# Electronic_Theremin.net
KiCad netlist of a schematic drawn in Altium Designer
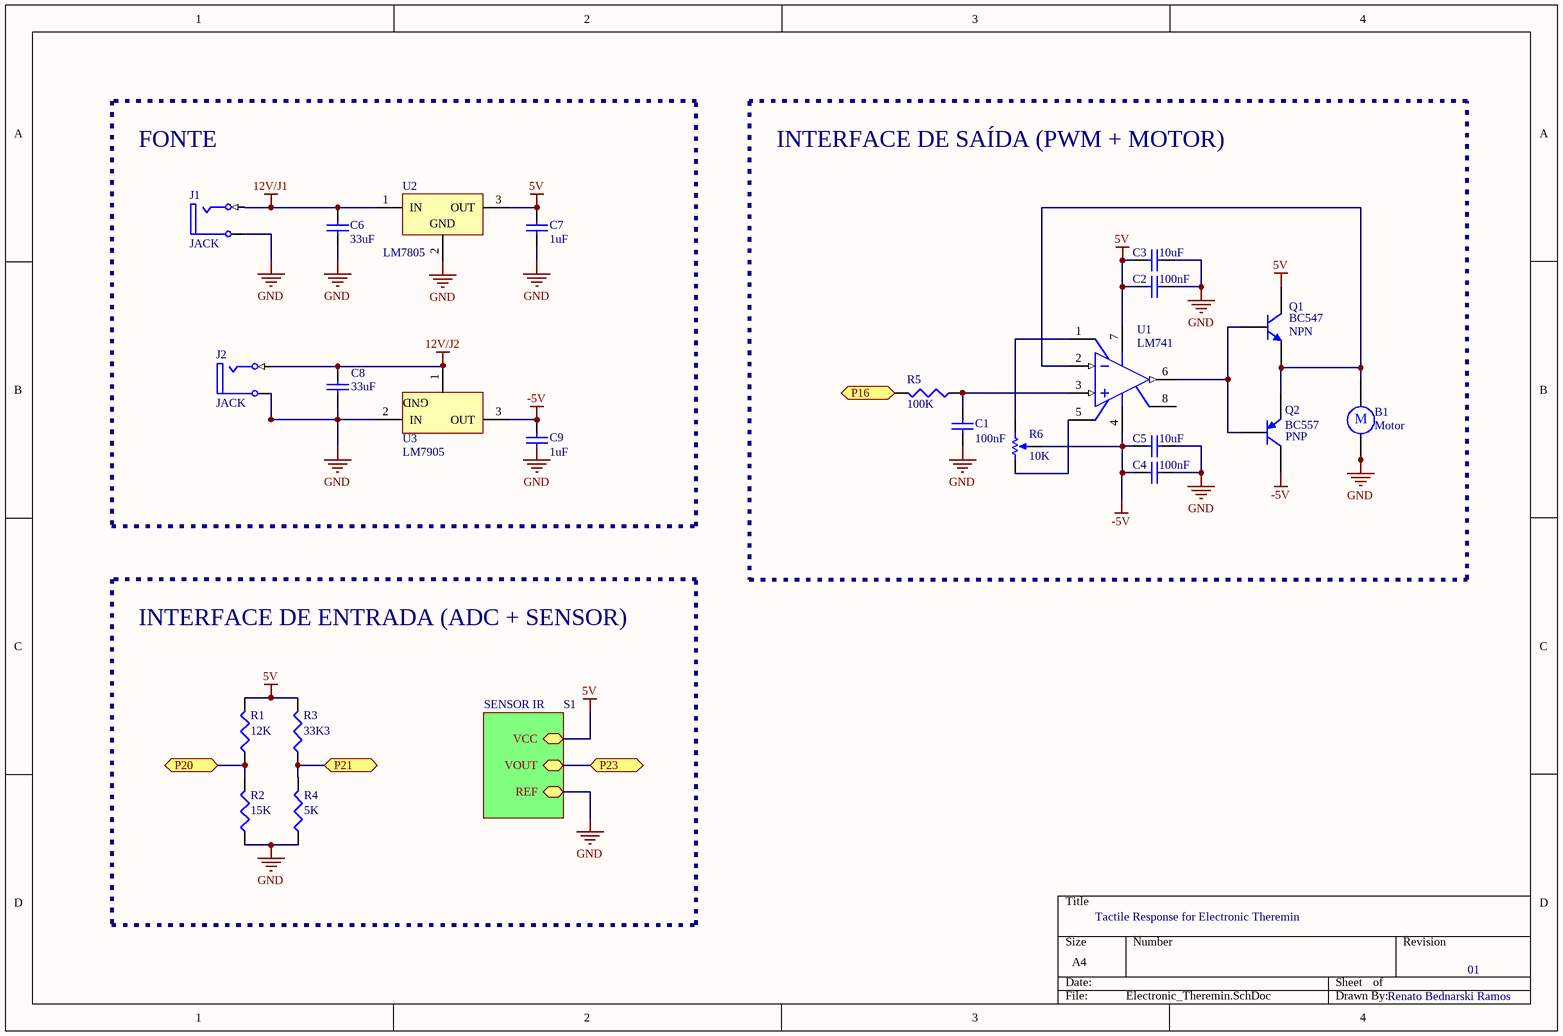
[diagram p0: Electronic_Theremin.SchDoc]

(export (version "E")
  (design (tool "Eeschema 10.0.6"))
  (components
    (comp (ref "B1")
      (value "Motor")
      (footprint "RB5-10.5")
      (description "Motor, General Kind")
      (fields (field (name "PUBLISHER") "Altium Limited"))
      (libsource (lib "Miscellaneous Devices") (part "Motor"))
    )
    (comp (ref "C1")
      (value "100nF")
      (footprint "RAD-0.3")
      (description "Capacitor")
      (fields (field (name "Comment") "Cap") (field (name "PUBLISHER") "Altium Limited"))
      (libsource (lib "Miscellaneous Devices") (part "Cap"))
    )
    (comp (ref "C2")
      (value "100nF")
      (footprint "RAD-0.3")
      (description "Capacitor")
      (fields (field (name "Comment") "Cap") (field (name "PUBLISHER") "Altium Limited"))
      (libsource (lib "Miscellaneous Devices") (part "Cap"))
    )
    (comp (ref "C3")
      (value "10uF")
      (footprint "RAD-0.3")
      (description "Capacitor")
      (fields (field (name "Comment") "Cap") (field (name "PUBLISHER") "Altium Limited"))
      (libsource (lib "Miscellaneous Devices") (part "Cap"))
    )
    (comp (ref "C4")
      (value "100nF")
      (footprint "RAD-0.3")
      (description "Capacitor")
      (fields (field (name "Comment") "Cap") (field (name "PUBLISHER") "Altium Limited"))
      (libsource (lib "Miscellaneous Devices") (part "Cap"))
    )
    (comp (ref "C5")
      (value "10uF")
      (footprint "RAD-0.3")
      (description "Capacitor")
      (fields (field (name "Comment") "Cap") (field (name "PUBLISHER") "Altium Limited"))
      (libsource (lib "Miscellaneous Devices") (part "Cap"))
    )
    (comp (ref "C6")
      (value "33uF")
      (footprint "RAD-0.3")
      (description "Capacitor")
      (fields (field (name "Comment") "Cap") (field (name "PUBLISHER") "Altium Limited"))
      (libsource (lib "Miscellaneous Devices") (part "Cap"))
    )
    (comp (ref "C7")
      (value "1uF")
      (footprint "RAD-0.3")
      (description "Capacitor")
      (fields (field (name "Comment") "Cap") (field (name "PUBLISHER") "Altium Limited"))
      (libsource (lib "Miscellaneous Devices") (part "Cap"))
    )
    (comp (ref "C8")
      (value "33uF")
      (footprint "RAD-0.3")
      (description "Capacitor")
      (fields (field (name "Comment") "Cap") (field (name "PUBLISHER") "Altium Limited"))
      (libsource (lib "Miscellaneous Devices") (part "Cap"))
    )
    (comp (ref "C9")
      (value "1uF")
      (footprint "RAD-0.3")
      (description "Capacitor")
      (fields (field (name "Comment") "Cap") (field (name "PUBLISHER") "Altium Limited"))
      (libsource (lib "Miscellaneous Devices") (part "Cap"))
    )
    (comp (ref "J1")
      (value "JACK")
      (footprint "JACK/6-V2")
      (description "Jack Socket, 1/4\" [6.5mm], Thru-Hole, Vertical, 2-Conductor Open Circuit")
      (fields (field (name "PUBLISHER") "Altium Limited"))
      (libsource (lib "Miscellaneous Connectors") (part "Phonejack2"))
    )
    (comp (ref "J2")
      (value "JACK")
      (footprint "JACK/6-V2")
      (description "Jack Socket, 1/4\" [6.5mm], Thru-Hole, Vertical, 2-Conductor Open Circuit")
      (fields (field (name "PUBLISHER") "Altium Limited"))
      (libsource (lib "Miscellaneous Connectors") (part "Phonejack2"))
    )
    (comp (ref "Q1")
      (value "NPN")
      (footprint "TO-226-AA")
      (description "NPN Bipolar Transistor")
      (fields (field (name "ALTIUM_VALUE") "BC547"))
      (libsource (lib "Miscellaneous Devices") (part "NPN"))
    )
    (comp (ref "Q2")
      (value "PNP")
      (footprint "SOT-23B_N")
      (description "PNP Bipolar Transistor")
      (fields (field (name "ALTIUM_VALUE") "BC557"))
      (libsource (lib "Miscellaneous Devices") (part "PNP"))
    )
    (comp (ref "R1")
      (value "12K")
      (footprint "J1-0603")
      (description "Resistor")
      (fields (field (name "Comment") "Res3") (field (name "PUBLISHER") "Altium Limited"))
      (libsource (lib "Miscellaneous Devices") (part "Res3"))
    )
    (comp (ref "R2")
      (value "15K")
      (footprint "J1-0603")
      (description "Resistor")
      (fields (field (name "Comment") "Res3") (field (name "PUBLISHER") "Altium Limited"))
      (libsource (lib "Miscellaneous Devices") (part "Res3"))
    )
    (comp (ref "R3")
      (value "33K3")
      (footprint "J1-0603")
      (description "Resistor")
      (fields (field (name "Comment") "Res3") (field (name "PUBLISHER") "Altium Limited"))
      (libsource (lib "Miscellaneous Devices") (part "Res3"))
    )
    (comp (ref "R4")
      (value "5K")
      (footprint "J1-0603")
      (description "Resistor")
      (fields (field (name "Comment") "Res3") (field (name "PUBLISHER") "Altium Limited"))
      (libsource (lib "Miscellaneous Devices") (part "Res3"))
    )
    (comp (ref "R5")
      (value "100K")
      (footprint "J1-0603")
      (description "Resistor")
      (fields (field (name "Comment") "Res3") (field (name "PUBLISHER") "Altium Limited"))
      (libsource (lib "Miscellaneous Devices") (part "Res3"))
    )
    (comp (ref "R6")
      (value "10K")
      (footprint "VR5")
      (description "Potentiometer")
      (fields (field (name "PUBLISHER") "Altium Limited"))
      (libsource (lib "Miscellaneous Devices") (part "RPot"))
    )
    (comp (ref "U1")
      (value "LM741")
      (footprint "N08E")
      (description "Operational Amplifier, 8-pin MDIP")
      (fields
        (field (name "PARTNUMBER") "LM741CN")
        (field (name "MANUFACTURER") "National Semiconductor")
        (field (name "PUBLISHER") "Altium Limited")
      )
      (libsource (lib "NSC Amplifier") (part "LM741CN"))
    )
    (comp (ref "U2")
      (value "LM7805")
      (footprint "KC03")
      (description "Positive-Voltage Regulator")
      (fields (field (name "PUBLISHER") "Altium Limited"))
      (libsource (lib "TI Power Mgt Voltage Regulator") (part "µA7805CKC"))
    )
    (comp (ref "U3")
      (value "LM7905")
      (footprint "T03B")
      (description "3-Terminal Negative Regulator, 3-pin TO-220")
      (fields
        (field (name "PARTNUMBER") "LM7905CT")
        (field (name "MANUFACTURER") "National Semiconductor")
        (field (name "PUBLISHER") "Altium Limited")
      )
      (libsource (lib "NSC LDO") (part "LM7905CT"))
    )
  )
  (nets
    (net (code "1") (name "-5V") (class "Default")
      (node (ref "C4") (pin "2") (pinfunction "2_2") (pintype "passive"))
      (node (ref "C5") (pin "2") (pinfunction "2_2") (pintype "passive"))
      (node (ref "C9") (pin "2") (pinfunction "2_2") (pintype "passive"))
      (node (ref "Q2") (pin "1") (pinfunction "C_1") (pintype "passive"))
      (node (ref "R6") (pin "3") (pinfunction "TAP_3") (pintype "passive"))
      (node (ref "U1") (pin "4") (pinfunction "V-_4") (pintype "power_in"))
      (node (ref "U3") (pin "3") (pinfunction "OUT_3") (pintype "power_in"))
    )
    (net (code "2") (name "/P16") (class "Default")
      (node (ref "R5") (pin "2") (pinfunction "2_2") (pintype "passive"))
    )
    (net (code "3") (name "/P20") (class "Default")
      (node (ref "R1") (pin "1") (pinfunction "1_1") (pintype "passive"))
      (node (ref "R2") (pin "2") (pinfunction "2_2") (pintype "passive"))
    )
    (net (code "4") (name "/P21") (class "Default")
      (node (ref "R3") (pin "1") (pinfunction "1_1") (pintype "passive"))
      (node (ref "R4") (pin "2") (pinfunction "2_2") (pintype "passive"))
    )
    (net (code "6") (name "5V") (class "Default")
      (node (ref "C2") (pin "2") (pinfunction "2_2") (pintype "passive"))
      (node (ref "C3") (pin "2") (pinfunction "2_2") (pintype "passive"))
      (node (ref "C7") (pin "2") (pinfunction "2_2") (pintype "passive"))
      (node (ref "Q1") (pin "1") (pinfunction "C_1") (pintype "passive"))
      (node (ref "R1") (pin "2") (pinfunction "2_2") (pintype "passive"))
      (node (ref "R3") (pin "2") (pinfunction "2_2") (pintype "passive"))
      (node (ref "U1") (pin "7") (pinfunction "V+_7") (pintype "power_in"))
      (node (ref "U2") (pin "3") (pinfunction "OUT_3") (pintype "power_in"))
    )
    (net (code "7") (name "12V{slash}J1") (class "Default")
      (node (ref "C6") (pin "2") (pinfunction "2_2") (pintype "passive"))
      (node (ref "J1") (pin "1") (pinfunction "T_1") (pintype "input"))
      (node (ref "U2") (pin "1") (pinfunction "IN_1") (pintype "power_in"))
    )
    (net (code "8") (name "12V{slash}J2") (class "Default")
      (node (ref "C8") (pin "2") (pinfunction "2_2") (pintype "passive"))
      (node (ref "J2") (pin "1") (pinfunction "T_1") (pintype "input"))
      (node (ref "U3") (pin "1") (pinfunction "GND_1") (pintype "power_in"))
    )
    (net (code "9") (name "GND") (class "Default")
      (node (ref "C1") (pin "1") (pinfunction "1_1") (pintype "passive"))
      (node (ref "C2") (pin "1") (pinfunction "1_1") (pintype "passive"))
      (node (ref "C3") (pin "1") (pinfunction "1_1") (pintype "passive"))
      (node (ref "C4") (pin "1") (pinfunction "1_1") (pintype "passive"))
      (node (ref "C5") (pin "1") (pinfunction "1_1") (pintype "passive"))
      (node (ref "C6") (pin "1") (pinfunction "1_1") (pintype "passive"))
      (node (ref "C7") (pin "1") (pinfunction "1_1") (pintype "passive"))
      (node (ref "C8") (pin "1") (pinfunction "1_1") (pintype "passive"))
      (node (ref "J1") (pin "5") (pinfunction "S_5") (pintype "power_in"))
      (node (ref "J2") (pin "5") (pinfunction "S_5") (pintype "power_in"))
      (node (ref "R2") (pin "1") (pinfunction "1_1") (pintype "passive"))
      (node (ref "R4") (pin "1") (pinfunction "1_1") (pintype "passive"))
      (node (ref "U2") (pin "2") (pinfunction "GND_2") (pintype "power_in"))
      (node (ref "U3") (pin "2") (pinfunction "IN_2") (pintype "power_in"))
    )
    (net (code "10") (name "Net-(Q1-B)") (class "Default")
      (node (ref "Q1") (pin "2") (pinfunction "B_2") (pintype "passive"))
      (node (ref "Q2") (pin "2") (pinfunction "B_2") (pintype "passive"))
      (node (ref "U1") (pin "6") (pinfunction "OUT_6") (pintype "output"))
    )
    (net (code "11") (name "Net-(Q1-E)") (class "Default")
      (node (ref "B1") (pin "1") (pinfunction "1_1") (pintype "passive"))
      (node (ref "Q1") (pin "3") (pinfunction "E_3") (pintype "passive"))
      (node (ref "Q2") (pin "3") (pinfunction "E_3") (pintype "passive"))
      (node (ref "U1") (pin "2") (pinfunction "IN-_2") (pintype "input"))
    )
    (net (code "12") (name "Net-(R6-BOT)") (class "Default")
      (node (ref "R6") (pin "2") (pinfunction "BOT_2") (pintype "passive"))
      (node (ref "U1") (pin "1") (pinfunction "OFS_NULL_1") (pintype "passive"))
    )
    (net (code "13") (name "Net-(R6-TOP)") (class "Default")
      (node (ref "R6") (pin "1") (pinfunction "TOP_1") (pintype "passive"))
      (node (ref "U1") (pin "5") (pinfunction "OFS_NULL_5") (pintype "passive"))
    )
    (net (code "14") (name "Net-(U1-IN+)") (class "Default")
      (node (ref "C1") (pin "2") (pinfunction "2_2") (pintype "passive"))
      (node (ref "R5") (pin "1") (pinfunction "1_1") (pintype "passive"))
      (node (ref "U1") (pin "3") (pinfunction "IN+_3") (pintype "input"))
    )
    (net (code "15") (name "unconnected-(B1-Pad2)") (class "Default")
      (node (ref "B1") (pin "2") (pinfunction "2_2") (pintype "passive"))
    )
    (net (code "16") (name "unconnected-(C9-Pad1)") (class "Default")
      (node (ref "C9") (pin "1") (pinfunction "1_1") (pintype "passive"))
    )
    (net (code "17") (name "unconnected-(U1-NC-Pad8)") (class "Default")
      (node (ref "U1") (pin "8") (pinfunction "NC_8") (pintype "passive"))
    )
  )
)
